# 3_6_1--esp32_-_0825.net
KiCad netlist of a schematic drawn in EasyEDA Pro
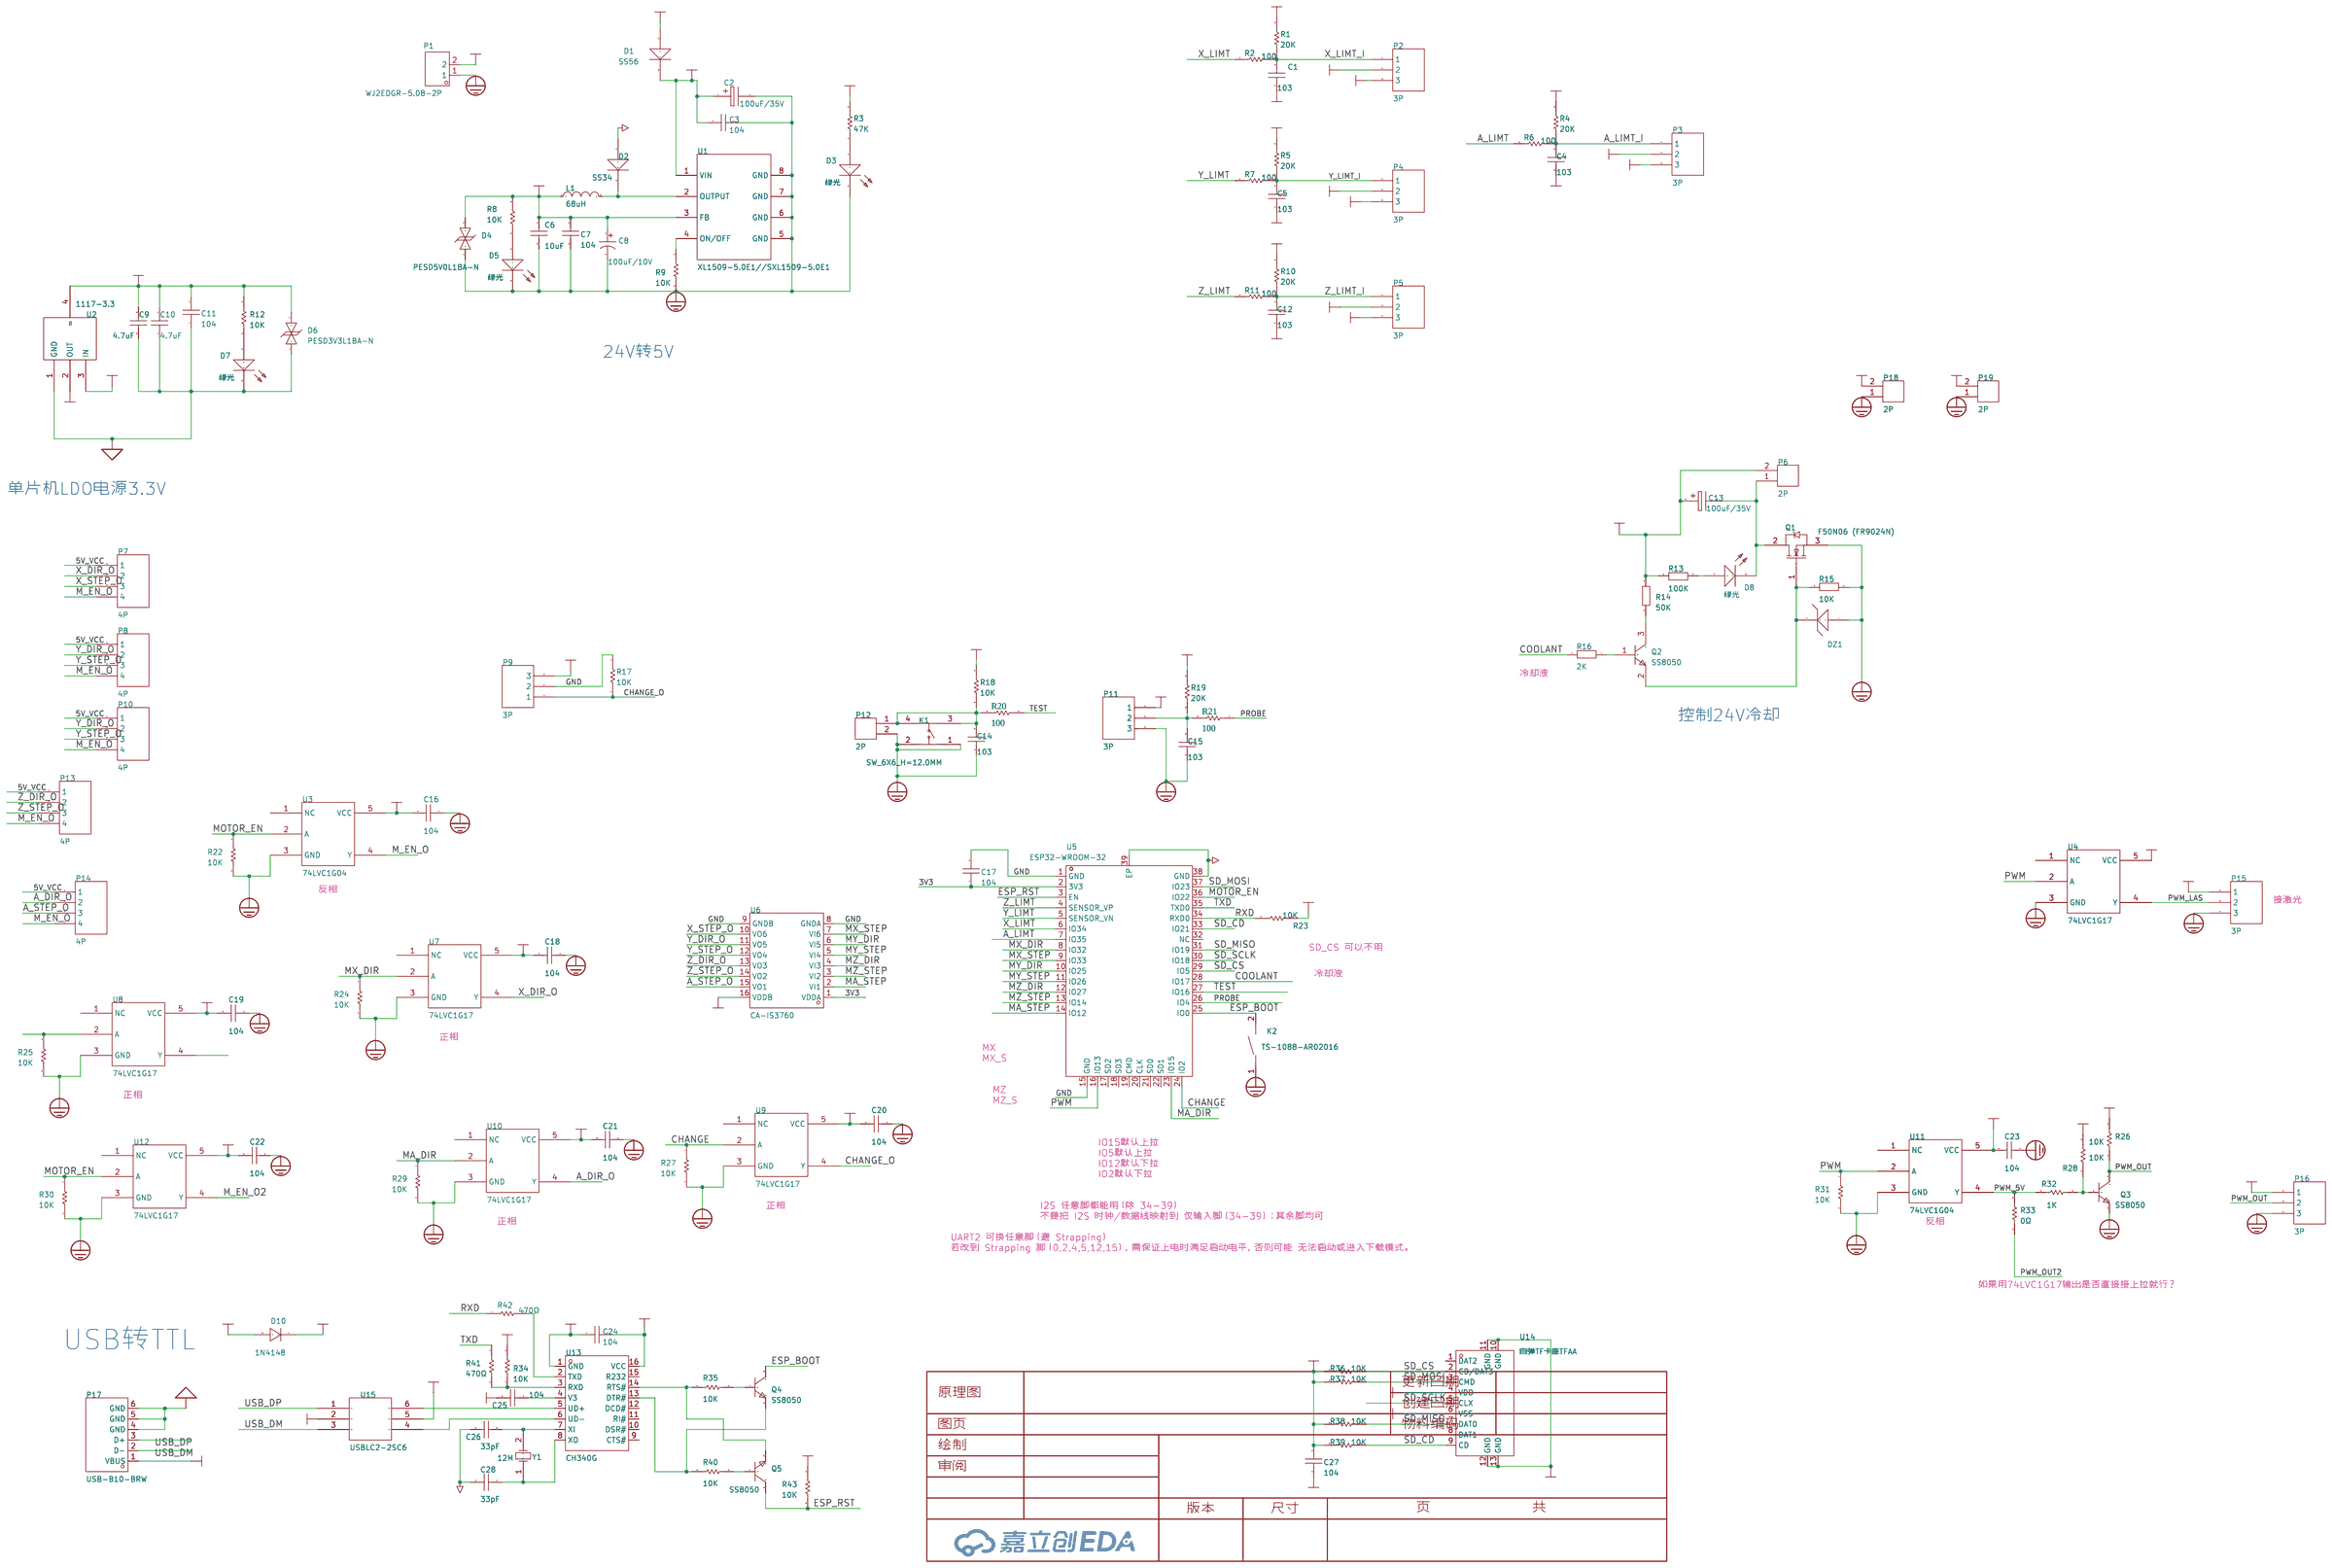
[diagram p0: schematic sheet]

(export (version "E")
  (design (tool "Eeschema 10.0.6"))
  (components
    (comp (ref "C1") (value "103") (footprint "easyedapro:11") (libsource (lib "easyedapro") (part "CAP")))
    (comp (ref "C2")
      (value "100uF/35V")
      (footprint "easyedapro:电解电容贴片10x10")
      (libsource (lib "easyedapro") (part "ELECTRO1"))
    )
    (comp (ref "C3")
      (value "104")
      (footprint "easyedapro:0603C")
      (description "Capacitor (Semiconductor SIM Model)")
      (libsource (lib "easyedapro") (part "Cap Semi"))
    )
    (comp (ref "C4") (value "103") (footprint "easyedapro:11") (libsource (lib "easyedapro") (part "CAP")))
    (comp (ref "C5") (value "103") (footprint "easyedapro:11") (libsource (lib "easyedapro") (part "CAP")))
    (comp (ref "C6") (value "10uF") (libsource (lib "") (part "CAP_1")))
    (comp (ref "C7")
      (value "104")
      (footprint "easyedapro:0603C")
      (description "Capacitor (Semiconductor SIM Model)")
      (libsource (lib "easyedapro") (part "Cap Semi"))
    )
    (comp (ref "C8")
      (value "100uF/10V")
      (footprint "easyedapro:CAP-SMD_BD5.0-L5.3-W5.3-RD")
      (fields (field (name "Manufacturer Part") "CS1A101M-CRD54") (field (name "Manufacturer") "ST(先科)"))
      (libsource (lib "easyedapro") (part "CS1A101M-CRD54"))
    )
    (comp (ref "C9") (value "4.7uF") (libsource (lib "") (part "CAP_1")))
    (comp (ref "C10") (value "4.7uF") (libsource (lib "") (part "CAP_1")))
    (comp (ref "C11")
      (value "104")
      (footprint "easyedapro:0603C")
      (description "Capacitor (Semiconductor SIM Model)")
      (libsource (lib "easyedapro") (part "Cap Semi"))
    )
    (comp (ref "C12") (value "103") (footprint "easyedapro:11") (libsource (lib "easyedapro") (part "CAP")))
    (comp (ref "C13")
      (value "100uF/35V")
      (footprint "easyedapro:电解电容贴片10x10")
      (libsource (lib "easyedapro") (part "ELECTRO1"))
    )
    (comp (ref "C14") (value "103") (footprint "easyedapro:11") (libsource (lib "easyedapro") (part "CAP")))
    (comp (ref "C15") (value "103") (footprint "easyedapro:11") (libsource (lib "easyedapro") (part "CAP")))
    (comp (ref "C16")
      (value "104")
      (footprint "easyedapro:0603C")
      (description "Capacitor (Semiconductor SIM Model)")
      (libsource (lib "easyedapro") (part "Cap Semi"))
    )
    (comp (ref "C17")
      (value "104")
      (footprint "easyedapro:0603C")
      (description "Capacitor (Semiconductor SIM Model)")
      (libsource (lib "easyedapro") (part "Cap Semi"))
    )
    (comp (ref "C18")
      (value "104")
      (footprint "easyedapro:0603C")
      (description "Capacitor (Semiconductor SIM Model)")
      (libsource (lib "easyedapro") (part "Cap Semi"))
    )
    (comp (ref "C19")
      (value "104")
      (footprint "easyedapro:0603C")
      (description "Capacitor (Semiconductor SIM Model)")
      (libsource (lib "easyedapro") (part "Cap Semi"))
    )
    (comp (ref "C20")
      (value "104")
      (footprint "easyedapro:0603C")
      (description "Capacitor (Semiconductor SIM Model)")
      (libsource (lib "easyedapro") (part "Cap Semi"))
    )
    (comp (ref "C21")
      (value "104")
      (footprint "easyedapro:0603C")
      (description "Capacitor (Semiconductor SIM Model)")
      (libsource (lib "easyedapro") (part "Cap Semi"))
    )
    (comp (ref "C22")
      (value "104")
      (footprint "easyedapro:0603C")
      (description "Capacitor (Semiconductor SIM Model)")
      (libsource (lib "easyedapro") (part "Cap Semi"))
    )
    (comp (ref "C23")
      (value "104")
      (footprint "easyedapro:0603C")
      (description "Capacitor (Semiconductor SIM Model)")
      (libsource (lib "easyedapro") (part "Cap Semi"))
    )
    (comp (ref "C24")
      (value "104")
      (footprint "easyedapro:0603C")
      (description "Capacitor (Semiconductor SIM Model)")
      (libsource (lib "easyedapro") (part "Cap Semi"))
    )
    (comp (ref "C25")
      (value "104")
      (footprint "easyedapro:0603C")
      (description "Capacitor (Semiconductor SIM Model)")
      (libsource (lib "easyedapro") (part "Cap Semi"))
    )
    (comp (ref "C26")
      (value "18pF")
      (footprint "easyedapro:0603C")
      (description "Capacitor (Semiconductor SIM Model)")
      (libsource (lib "easyedapro") (part "Cap Semi"))
    )
    (comp (ref "C27")
      (value "104")
      (footprint "easyedapro:11")
      (description "Capacitor (Semiconductor SIM Model)")
      (libsource (lib "easyedapro") (part "Cap Semi"))
    )
    (comp (ref "C28")
      (value "18pF")
      (footprint "easyedapro:0603C")
      (description "Capacitor (Semiconductor SIM Model)")
      (libsource (lib "easyedapro") (part "Cap Semi"))
    )
    (comp (ref "D1") (value "SS56") (footprint "easyedapro:SMA") (libsource (lib "") (part "1N4148_1")))
    (comp (ref "D2") (value "SS34") (libsource (lib "easyedapro") (part "1N4148")))
    (comp (ref "D3")
      (value "绿光")
      (footprint "easyedapro:0603LED")
      (libsource (lib "easyedapro") (part "LED"))
    )
    (comp (ref "D4")
      (value "PESD5V0L1BA-N")
      (footprint "easyedapro:SOD-523_L1.2-W0.8-LS1.6-BI")
      (description "极性:Bidirectional;反向关断电压（典型值）:5V (Max);击穿电压（最小值）:6V;箝位电压:15V;峰值脉冲电流（10/1000us）:5A (8/20us);")
      (fields (field (name "Manufacturer") "BORN伯恩半导体"))
      (libsource (lib "easyedapro") (part "PESD5V0S1BBN"))
    )
    (comp (ref "D5")
      (value "绿光")
      (footprint "easyedapro:0603LED")
      (libsource (lib "easyedapro") (part "LED"))
    )
    (comp (ref "D6")
      (value "PESD3V3L1BA-N")
      (footprint "easyedapro:SOD-523_L1.2-W0.8-LS1.6-BI")
      (description "极性:Bidirectional;反向关断电压（典型值）:5V (Max);击穿电压（最小值）:6V;箝位电压:15V;峰值脉冲电流（10/1000us）:5A (8/20us);")
      (fields (field (name "Manufacturer") "BORN伯恩半导体"))
      (libsource (lib "easyedapro") (part "PESD5V0S1BBN"))
    )
    (comp (ref "D7")
      (value "绿光")
      (footprint "easyedapro:0603LED")
      (libsource (lib "easyedapro") (part "LED"))
    )
    (comp (ref "D8")
      (value "绿光")
      (footprint "easyedapro:0603LED")
      (libsource (lib "easyedapro") (part "LED"))
    )
    (comp (ref "D10")
      (value "1N4148")
      (footprint "easyedapro:SOD-123_L2.8-W1.8-LS3.7-RD")
      (fields (field (name "Manufacturer") "MCC(美微科)"))
      (libsource (lib "easyedapro") (part "1N4148W-TP"))
    )
    (comp (ref "DZ1") (value "--ѹ------SMAZ10V") (libsource (lib "easyedapro") (part "ѹ")))
    (comp (ref "K1")
      (value "SW_6X6_H=12.0MM")
      (footprint "easyedapro:KEY-SMD_4P-L6.0-W6.0-P4.50-LS9.0")
      (libsource (lib "easyedapro") (part "SW_6X6_H=12.0MM"))
    )
    (comp (ref "K2")
      (value "TS-1088-AR02016")
      (footprint "easyedapro:SW-SMD_L3.9-W3.0-P4.45")
      (fields (field (name "Manufacturer") "XUNPU(讯普)"))
      (libsource (lib "easyedapro") (part "TS-1088-AR02016"))
    )
    (comp (ref "L1")
      (value "68uH")
      (footprint "easyedapro:IND-SMD_L7.0-W7.0_SMDRI74-330MT")
      (description "电感值:33uH;精度:±20%;额定电流:960mA;饱和电流(Isat):1.8A;类型:屏蔽电感;")
      (fields (field (name "Manufacturer Part") "SMDRI74-330MT") (field (name "Manufacturer") "SXN(顺翔诺)"))
      (libsource (lib "easyedapro") (part "SMDRI74-330MT"))
    )
    (comp (ref "P1")
      (value "WJ2EDGR-5.08-2P")
      (footprint "easyedapro:CONN-TH_WJ2EDGR-5.08-2P")
      (description "每排PIN数:2;安装方式:弯针;排数:1;间距:5.08mm;连接器类型:板端/插座-开口;")
      (fields (field (name "Manufacturer") "KANGNEX(康奈克斯电气)"))
      (libsource (lib "easyedapro") (part "WJ2EDGR-5.08-2P"))
    )
    (comp (ref "P2")
      (value "3P")
      (footprint "easyedapro:HDR1X3_CON")
      (libsource (lib "easyedapro") (part "3P"))
    )
    (comp (ref "P3")
      (value "3P")
      (footprint "easyedapro:HDR1X3_CON")
      (libsource (lib "easyedapro") (part "3P"))
    )
    (comp (ref "P4")
      (value "3P")
      (footprint "easyedapro:HDR1X3_CON")
      (libsource (lib "easyedapro") (part "3P"))
    )
    (comp (ref "P5")
      (value "3P")
      (footprint "easyedapro:HDR1X3_CON")
      (libsource (lib "easyedapro") (part "3P"))
    )
    (comp (ref "P6")
      (value "2P")
      (footprint "easyedapro:HDR1X2_CON")
      (libsource (lib "easyedapro") (part "2P"))
    )
    (comp (ref "P7")
      (value "4P")
      (footprint "easyedapro:HDR1X4_CON")
      (libsource (lib "easyedapro") (part "4P"))
    )
    (comp (ref "P8")
      (value "4P")
      (footprint "easyedapro:HDR1X4_CON")
      (libsource (lib "easyedapro") (part "4P"))
    )
    (comp (ref "P9")
      (value "3P")
      (footprint "easyedapro:HDR1X3_CON")
      (libsource (lib "easyedapro") (part "3P"))
    )
    (comp (ref "P10")
      (value "4P")
      (footprint "easyedapro:HDR1X4_CON")
      (libsource (lib "easyedapro") (part "4P"))
    )
    (comp (ref "P11")
      (value "3P")
      (footprint "easyedapro:HDR1X3_CON")
      (libsource (lib "easyedapro") (part "3P"))
    )
    (comp (ref "P12")
      (value "2P")
      (footprint "easyedapro:HDR1X2_CON")
      (libsource (lib "easyedapro") (part "2P"))
    )
    (comp (ref "P13")
      (value "4P")
      (footprint "easyedapro:HDR1X4_CON")
      (libsource (lib "easyedapro") (part "4P"))
    )
    (comp (ref "P14")
      (value "4P")
      (footprint "easyedapro:HDR1X4_CON")
      (libsource (lib "easyedapro") (part "4P"))
    )
    (comp (ref "P15")
      (value "3P")
      (footprint "easyedapro:HDR1X3_CON")
      (libsource (lib "easyedapro") (part "3P"))
    )
    (comp (ref "P16")
      (value "3P")
      (footprint "easyedapro:HDR1X3_CON")
      (libsource (lib "easyedapro") (part "3P"))
    )
    (comp (ref "P17")
      (value "USB-B10-BRW")
      (footprint "easyedapro:USB-B-TH_USB-B10-BRW")
      (fields (field (name "Manufacturer") "XUNPU(讯普)"))
      (libsource (lib "easyedapro") (part "USB-B10-BRW"))
    )
    (comp (ref "P18")
      (value "2P")
      (footprint "easyedapro:HDR1X2_CON")
      (libsource (lib "easyedapro") (part "2P"))
    )
    (comp (ref "P19")
      (value "2P")
      (footprint "easyedapro:HDR1X2_CON")
      (libsource (lib "easyedapro") (part "2P"))
    )
    (comp (ref "Q1")
      (value "F50N06 (FR9024N)")
      (footprint "easyedapro:TO-252")
      (description "N-Channel Power MOSFET")
      (libsource (lib "easyedapro") (part "NMOS-2"))
    )
    (comp (ref "Q2")
      (value "SS8050")
      (footprint "easyedapro:SOT-23")
      (description "NPN General Purpose Amplifier")
      (libsource (lib "easyedapro") (part "2N3904"))
    )
    (comp (ref "Q3")
      (value "SS8050")
      (footprint "easyedapro:SOT-23-3_L2.9-W1.3-P1.90-LS2.4-BR")
      (fields (field (name "Manufacturer") "CJ（江苏长电/长晶）"))
      (libsource (lib "easyedapro") (part "SS8050_C2150"))
    )
    (comp (ref "Q4")
      (value "SS8050")
      (footprint "easyedapro:SOT-23-3_L2.9-W1.3-P1.90-LS2.4-BR")
      (fields (field (name "Manufacturer") "Doeshare(德芯)"))
      (libsource (lib "easyedapro") (part "SS8050_C2931717"))
    )
    (comp (ref "Q5")
      (value "SS8050")
      (footprint "easyedapro:SOT-23-3_L2.9-W1.3-P1.90-LS2.4-BR")
      (fields (field (name "Manufacturer") "Doeshare(德芯)"))
      (libsource (lib "easyedapro") (part "SS8050_C2931717"))
    )
    (comp (ref "R1")
      (value "20K")
      (footprint "easyedapro:10")
      (description "Resistor")
      (libsource (lib "") (part "RES_1"))
    )
    (comp (ref "R2")
      (value "100")
      (footprint "easyedapro:10")
      (description "Resistor")
      (libsource (lib "") (part "RES_1"))
    )
    (comp (ref "R3")
      (value "47K")
      (footprint "easyedapro:0603R")
      (description "Resistor")
      (libsource (lib "") (part "RES_1"))
    )
    (comp (ref "R4")
      (value "20K")
      (footprint "easyedapro:10")
      (description "Resistor")
      (libsource (lib "") (part "RES_1"))
    )
    (comp (ref "R5")
      (value "20K")
      (footprint "easyedapro:10")
      (description "Resistor")
      (libsource (lib "") (part "RES_1"))
    )
    (comp (ref "R6")
      (value "100")
      (footprint "easyedapro:10")
      (description "Resistor")
      (libsource (lib "") (part "RES_1"))
    )
    (comp (ref "R7")
      (value "100")
      (footprint "easyedapro:10")
      (description "Resistor")
      (libsource (lib "") (part "RES_1"))
    )
    (comp (ref "R8")
      (value "10K")
      (footprint "easyedapro:0603R")
      (description "Resistor")
      (libsource (lib "") (part "RES_1"))
    )
    (comp (ref "R9")
      (value "10K")
      (footprint "easyedapro:0603R")
      (description "Resistor")
      (libsource (lib "") (part "RES_1"))
    )
    (comp (ref "R10")
      (value "20K")
      (footprint "easyedapro:10")
      (description "Resistor")
      (libsource (lib "") (part "RES_1"))
    )
    (comp (ref "R11")
      (value "100")
      (footprint "easyedapro:10")
      (description "Resistor")
      (libsource (lib "") (part "RES_1"))
    )
    (comp (ref "R12")
      (value "10K")
      (footprint "easyedapro:0603R")
      (description "Resistor")
      (libsource (lib "") (part "RES_1"))
    )
    (comp (ref "R13")
      (value "100K")
      (footprint "easyedapro:0603R")
      (libsource (lib "easyedapro") (part "res"))
    )
    (comp (ref "R14")
      (value "50K")
      (footprint "easyedapro:0603R")
      (libsource (lib "easyedapro") (part "res"))
    )
    (comp (ref "R15")
      (value "10K")
      (footprint "easyedapro:0603R")
      (libsource (lib "easyedapro") (part "res"))
    )
    (comp (ref "R16") (value "2K") (footprint "easyedapro:0603R") (libsource (lib "easyedapro") (part "res")))
    (comp (ref "R17")
      (value "10K")
      (footprint "easyedapro:0603R")
      (description "Resistor")
      (libsource (lib "") (part "RES_1"))
    )
    (comp (ref "R18")
      (value "10K")
      (footprint "easyedapro:0603R")
      (description "Resistor")
      (libsource (lib "") (part "RES_1"))
    )
    (comp (ref "R19")
      (value "10K")
      (footprint "easyedapro:0603R")
      (description "Resistor")
      (libsource (lib "") (part "RES_1"))
    )
    (comp (ref "R20")
      (value "100")
      (description "Resistor")
      (fields (field (name "Publisher") "Altium Limited"))
      (libsource (lib "easyedapro") (part "RES"))
    )
    (comp (ref "R21")
      (value "100")
      (description "Resistor")
      (fields (field (name "Publisher") "Altium Limited"))
      (libsource (lib "easyedapro") (part "RES"))
    )
    (comp (ref "R22")
      (value "10K")
      (description "Resistor")
      (fields (field (name "Publisher") "Altium Limited"))
      (libsource (lib "easyedapro") (part "RES"))
    )
    (comp (ref "R23")
      (value "10K")
      (footprint "easyedapro:0603R")
      (description "Resistor")
      (libsource (lib "") (part "RES_1"))
    )
    (comp (ref "R24")
      (value "10K")
      (description "Resistor")
      (fields (field (name "Publisher") "Altium Limited"))
      (libsource (lib "easyedapro") (part "RES"))
    )
    (comp (ref "R25")
      (value "10K")
      (description "Resistor")
      (fields (field (name "Publisher") "Altium Limited"))
      (libsource (lib "easyedapro") (part "RES"))
    )
    (comp (ref "R26")
      (value "10K")
      (description "Resistor")
      (fields (field (name "Publisher") "Altium Limited"))
      (libsource (lib "easyedapro") (part "RES"))
    )
    (comp (ref "R27")
      (value "10K")
      (description "Resistor")
      (fields (field (name "Publisher") "Altium Limited"))
      (libsource (lib "easyedapro") (part "RES"))
    )
    (comp (ref "R28")
      (value "10K")
      (description "Resistor")
      (fields (field (name "Publisher") "Altium Limited"))
      (libsource (lib "easyedapro") (part "RES"))
    )
    (comp (ref "R29")
      (value "10K")
      (description "Resistor")
      (fields (field (name "Publisher") "Altium Limited"))
      (libsource (lib "easyedapro") (part "RES"))
    )
    (comp (ref "R30")
      (value "10K")
      (description "Resistor")
      (fields (field (name "Publisher") "Altium Limited"))
      (libsource (lib "easyedapro") (part "RES"))
    )
    (comp (ref "R31")
      (value "10K")
      (description "Resistor")
      (fields (field (name "Publisher") "Altium Limited"))
      (libsource (lib "easyedapro") (part "RES"))
    )
    (comp (ref "R32")
      (value "1K")
      (description "Resistor")
      (fields (field (name "Publisher") "Altium Limited"))
      (libsource (lib "easyedapro") (part "RES"))
    )
    (comp (ref "R33")
      (value "0Ω")
      (description "Resistor")
      (fields (field (name "Publisher") "Altium Limited"))
      (libsource (lib "easyedapro") (part "RES"))
    )
    (comp (ref "R34")
      (value "10K")
      (footprint "easyedapro:0603R")
      (description "Resistor")
      (libsource (lib "") (part "RES_1"))
    )
    (comp (ref "R35")
      (value "10K")
      (footprint "easyedapro:0603R")
      (description "Resistor")
      (libsource (lib "") (part "RES_1"))
    )
    (comp (ref "R36")
      (value "10K")
      (footprint "easyedapro:10")
      (description "Resistor")
      (libsource (lib "") (part "RES_1"))
    )
    (comp (ref "R37")
      (value "10K")
      (footprint "easyedapro:10")
      (description "Resistor")
      (libsource (lib "") (part "RES_1"))
    )
    (comp (ref "R38")
      (value "10K")
      (footprint "easyedapro:10")
      (description "Resistor")
      (libsource (lib "") (part "RES_1"))
    )
    (comp (ref "R39")
      (value "10K")
      (footprint "easyedapro:10")
      (description "Resistor")
      (libsource (lib "") (part "RES_1"))
    )
    (comp (ref "R40")
      (value "10K")
      (footprint "easyedapro:0603R")
      (description "Resistor")
      (libsource (lib "") (part "RES_1"))
    )
    (comp (ref "R41")
      (value "470Ω")
      (description "Resistor")
      (fields (field (name "Publisher") "Altium Limited"))
      (libsource (lib "easyedapro") (part "RES"))
    )
    (comp (ref "R42")
      (value "470Ω")
      (description "Resistor")
      (fields (field (name "Publisher") "Altium Limited"))
      (libsource (lib "easyedapro") (part "RES"))
    )
    (comp (ref "R43")
      (value "10K")
      (description "Resistor")
      (fields (field (name "Publisher") "Altium Limited"))
      (libsource (lib "easyedapro") (part "RES"))
    )
    (comp (ref "U1")
      (value "XL1509-5.0E1//SXL1509-5.0E1")
      (footprint "easyedapro:SOIC-8_L5.0-W4.0-P1.27-LS6.0-BL")
      (description "功能类型:降压型;同步整流:-;输出通道数:-;拓扑结构:-;输入电压:-;输出电流(最大值):-;开关频率:-;")
      (fields (field (name "Manufacturer") "XLSEMI(芯龙)"))
      (libsource (lib "easyedapro") (part "XL1509-5.0E1"))
    )
    (comp (ref "U2")
      (value "1117-3.3")
      (footprint "easyedapro:SOT-223")
      (libsource (lib "easyedapro") (part "LM1117"))
    )
    (comp (ref "U3")
      (value "74LVC1G04")
      (footprint "easyedapro:SMD8")
      (libsource (lib "easyedapro") (part "74LVC1G04"))
    )
    (comp (ref "U4")
      (value "74LVC1G17")
      (footprint "easyedapro:SMD8")
      (libsource (lib "easyedapro") (part "74LVC1G04"))
    )
    (comp (ref "U5")
      (value "ESP32-WROOM-32")
      (footprint "easyedapro:WIFIM-SMD_ESP-WROOM-32")
      (description "WiFi+双模蓝牙 双核CPU 网口 顶配MCU 低功耗蓝牙 ESP32系列ESP-WROOM-32模组/ESP-32S 4MB")
      (fields (field (name "Manufacturer") "ESPRESSIF(乐鑫)"))
      (libsource (lib "easyedapro") (part "ESP-WROOM-32"))
    )
    (comp (ref "U6")
      (value "CA-IS3760")
      (footprint "easyedapro:SOIC-16_L9.9-W3.9-P1.27-LS6.0-BL")
      (fields (field (name "Manufacturer") "Chipanalog(川土微)"))
      (libsource (lib "easyedapro") (part "CA-IS3760HN"))
    )
    (comp (ref "U7")
      (value "74LVC1G17")
      (footprint "easyedapro:SMD8")
      (libsource (lib "easyedapro") (part "74LVC1G04"))
    )
    (comp (ref "U8")
      (value "74LVC1G17")
      (footprint "easyedapro:SMD8")
      (libsource (lib "easyedapro") (part "74LVC1G04"))
    )
    (comp (ref "U9")
      (value "74LVC1G17")
      (footprint "easyedapro:SMD8")
      (libsource (lib "easyedapro") (part "74LVC1G04"))
    )
    (comp (ref "U10")
      (value "74LVC1G17")
      (footprint "easyedapro:SMD8")
      (libsource (lib "easyedapro") (part "74LVC1G04"))
    )
    (comp (ref "U11")
      (value "74LVC1G04")
      (footprint "easyedapro:SMD8")
      (libsource (lib "easyedapro") (part "74LVC1G04"))
    )
    (comp (ref "U12")
      (value "74LVC1G17")
      (footprint "easyedapro:SMD8")
      (libsource (lib "easyedapro") (part "74LVC1G04"))
    )
    (comp (ref "U13")
      (value "CH340G")
      (footprint "easyedapro:SOIC-16_L9.9-W3.9-P1.27-LS6.0-BL")
      (description "应用功能:收发器;接口协议:USB 2.0;数据速率:2Mbps;")
      (fields (field (name "Manufacturer") "WCH(南京沁恒)"))
      (libsource (lib "easyedapro") (part "CH340G"))
    )
    (comp (ref "U14")
      (value "自弹TF卡座TFAA")
      (footprint "easyedapro:SIM-SMD_C9900015645")
      (libsource (lib "easyedapro") (part "自弹TF卡座TFAA"))
    )
    (comp (ref "U15")
      (value "USBLC2-2SC6")
      (footprint "easyedapro:SOT-23-6")
      (libsource (lib "easyedapro") (part "DIP6"))
    )
    (comp (ref "Y1")
      (value "12M")
      (footprint "easyedapro:晶振贴片49SSMD")
      (description "Crystal Oscillator")
      (libsource (lib "easyedapro") (part "XTAL"))
    )
  )
  (nets
    (net (code "1") (name "/A_DIR_O") (class "Default")
      (node (ref "P14") (pin "2") (pinfunction "2_2") (pintype "unspecified"))
      (node (ref "U10") (pin "4") (pinfunction "Y_4") (pintype "unspecified"))
    )
    (net (code "2") (name "/A_LIMT") (class "Default")
      (node (ref "R6") (pin "2") (pinfunction "2_2") (pintype "unspecified"))
      (node (ref "U5") (pin "7") (pinfunction "IO35_7") (pintype "unspecified"))
    )
    (net (code "3") (name "/A_LIMT_I") (class "Default")
      (node (ref "C4") (pin "2") (pinfunction "2_2") (pintype "unspecified"))
      (node (ref "P3") (pin "1") (pinfunction "1_1") (pintype "unspecified"))
      (node (ref "R4") (pin "1") (pinfunction "1_1") (pintype "unspecified"))
      (node (ref "R6") (pin "1") (pinfunction "1_1") (pintype "unspecified"))
    )
    (net (code "4") (name "/A_STEP_O") (class "Default")
      (node (ref "P14") (pin "3") (pinfunction "3_3") (pintype "unspecified"))
      (node (ref "U6") (pin "15") (pinfunction "VO1_15") (pintype "unspecified"))
    )
    (net (code "5") (name "/CHANGE") (class "Default")
      (node (ref "R27") (pin "1") (pinfunction "1_1") (pintype "input"))
      (node (ref "U5") (pin "24") (pinfunction "IO2_24") (pintype "unspecified"))
      (node (ref "U9") (pin "2") (pinfunction "A_2") (pintype "unspecified"))
    )
    (net (code "6") (name "/CHANGE_O") (class "Default")
      (node (ref "P9") (pin "1") (pinfunction "1_1") (pintype "unspecified"))
      (node (ref "R17") (pin "2") (pinfunction "2_2") (pintype "unspecified"))
      (node (ref "U9") (pin "4") (pinfunction "Y_4") (pintype "unspecified"))
    )
    (net (code "7") (name "/COOLANT") (class "Default")
      (node (ref "R16") (pin "2") (pintype "unspecified"))
      (node (ref "U5") (pin "28") (pinfunction "IO17_28") (pintype "unspecified"))
    )
    (net (code "8") (name "/ESP_BOOT") (class "Default")
      (node (ref "K2") (pin "2") (pinfunction "2_2") (pintype "unspecified"))
      (node (ref "Q4") (pin "3") (pinfunction "C_3") (pintype "unspecified"))
      (node (ref "U5") (pin "25") (pinfunction "IO0_25") (pintype "unspecified"))
    )
    (net (code "9") (name "/ESP_RST") (class "Default")
      (node (ref "Q5") (pin "3") (pinfunction "C_3") (pintype "unspecified"))
      (node (ref "R43") (pin "2") (pinfunction "2_2") (pintype "input"))
      (node (ref "U5") (pin "3") (pinfunction "EN_3") (pintype "unspecified"))
    )
    (net (code "10") (name "/MA_DIR") (class "Default")
      (node (ref "R29") (pin "1") (pinfunction "1_1") (pintype "input"))
      (node (ref "U10") (pin "2") (pinfunction "A_2") (pintype "unspecified"))
      (node (ref "U5") (pin "23") (pinfunction "IO15_23") (pintype "unspecified"))
    )
    (net (code "11") (name "/MA_STEP") (class "Default")
      (node (ref "U5") (pin "14") (pinfunction "IO12_14") (pintype "unspecified"))
      (node (ref "U6") (pin "2") (pinfunction "VI1_2") (pintype "unspecified"))
    )
    (net (code "12") (name "/MOTOR_EN") (class "Default")
      (node (ref "R22") (pin "1") (pinfunction "1_1") (pintype "input"))
      (node (ref "R30") (pin "1") (pinfunction "1_1") (pintype "input"))
      (node (ref "U12") (pin "2") (pinfunction "A_2") (pintype "unspecified"))
      (node (ref "U3") (pin "2") (pinfunction "A_2") (pintype "unspecified"))
      (node (ref "U5") (pin "36") (pinfunction "IO22_36") (pintype "unspecified"))
    )
    (net (code "13") (name "/MX_DIR") (class "Default")
      (node (ref "R24") (pin "1") (pinfunction "1_1") (pintype "input"))
      (node (ref "U5") (pin "8") (pinfunction "IO32_8") (pintype "unspecified"))
      (node (ref "U7") (pin "2") (pinfunction "A_2") (pintype "unspecified"))
    )
    (net (code "14") (name "/MX_STEP") (class "Default")
      (node (ref "U5") (pin "9") (pinfunction "IO33_9") (pintype "unspecified"))
      (node (ref "U6") (pin "7") (pinfunction "VI6_7") (pintype "unspecified"))
    )
    (net (code "15") (name "/MY_DIR") (class "Default")
      (node (ref "U5") (pin "10") (pinfunction "IO25_10") (pintype "unspecified"))
      (node (ref "U6") (pin "6") (pinfunction "VI5_6") (pintype "unspecified"))
    )
    (net (code "16") (name "/MY_STEP") (class "Default")
      (node (ref "U5") (pin "11") (pinfunction "IO26_11") (pintype "unspecified"))
      (node (ref "U6") (pin "5") (pinfunction "VI4_5") (pintype "unspecified"))
    )
    (net (code "17") (name "/MZ_DIR") (class "Default")
      (node (ref "U5") (pin "12") (pinfunction "IO27_12") (pintype "unspecified"))
      (node (ref "U6") (pin "4") (pinfunction "VI3_4") (pintype "unspecified"))
    )
    (net (code "18") (name "/MZ_STEP") (class "Default")
      (node (ref "U5") (pin "13") (pinfunction "IO14_13") (pintype "unspecified"))
      (node (ref "U6") (pin "3") (pinfunction "VI2_3") (pintype "unspecified"))
    )
    (net (code "19") (name "/M_EN_O") (class "Default")
      (node (ref "P10") (pin "4") (pinfunction "4_4") (pintype "unspecified"))
      (node (ref "P13") (pin "4") (pinfunction "4_4") (pintype "unspecified"))
      (node (ref "P14") (pin "4") (pinfunction "4_4") (pintype "unspecified"))
      (node (ref "P7") (pin "4") (pinfunction "4_4") (pintype "unspecified"))
      (node (ref "P8") (pin "4") (pinfunction "4_4") (pintype "unspecified"))
      (node (ref "U3") (pin "4") (pinfunction "Y_4") (pintype "unspecified"))
    )
    (net (code "20") (name "/M_EN_O2") (class "Default")
      (node (ref "U12") (pin "4") (pinfunction "Y_4") (pintype "unspecified"))
    )
    (net (code "21") (name "/PROBE") (class "Default")
      (node (ref "R21") (pin "1") (pinfunction "1_1") (pintype "input"))
      (node (ref "U5") (pin "26") (pinfunction "IO4_26") (pintype "unspecified"))
    )
    (net (code "22") (name "/PWM") (class "Default")
      (node (ref "R31") (pin "1") (pinfunction "1_1") (pintype "input"))
      (node (ref "U11") (pin "2") (pinfunction "A_2") (pintype "unspecified"))
      (node (ref "U4") (pin "2") (pinfunction "A_2") (pintype "unspecified"))
      (node (ref "U5") (pin "16") (pinfunction "IO13_16") (pintype "unspecified"))
    )
    (net (code "23") (name "/PWM_5V") (class "Default")
      (node (ref "R32") (pin "1") (pinfunction "1_1") (pintype "input"))
      (node (ref "R33") (pin "2") (pinfunction "2_2") (pintype "input"))
      (node (ref "U11") (pin "4") (pinfunction "Y_4") (pintype "unspecified"))
    )
    (net (code "24") (name "/PWM_LAS") (class "Default")
      (node (ref "P15") (pin "2") (pinfunction "2_2") (pintype "unspecified"))
      (node (ref "U4") (pin "4") (pinfunction "Y_4") (pintype "unspecified"))
    )
    (net (code "25") (name "/PWM_OUT") (class "Default")
      (node (ref "P16") (pin "2") (pinfunction "2_2") (pintype "unspecified"))
      (node (ref "Q3") (pin "3") (pinfunction "C_3") (pintype "input"))
      (node (ref "R26") (pin "1") (pinfunction "1_1") (pintype "input"))
    )
    (net (code "26") (name "/PWM_OUT2") (class "Default")
      (node (ref "R33") (pin "1") (pinfunction "1_1") (pintype "input"))
    )
    (net (code "27") (name "/RXD") (class "Default")
      (node (ref "R23") (pin "2") (pinfunction "2_2") (pintype "unspecified"))
      (node (ref "R42") (pin "1") (pinfunction "1_1") (pintype "input"))
      (node (ref "U5") (pin "34") (pinfunction "RXD0_34") (pintype "unspecified"))
    )
    (net (code "28") (name "/SD_CD") (class "Default")
      (node (ref "R39") (pin "1") (pinfunction "1_1") (pintype "unspecified"))
      (node (ref "U14") (pin "9") (pinfunction "CD_9") (pintype "unspecified"))
      (node (ref "U5") (pin "33") (pinfunction "IO21_33") (pintype "unspecified"))
    )
    (net (code "29") (name "/SD_CS") (class "Default")
      (node (ref "R36") (pin "1") (pinfunction "1_1") (pintype "unspecified"))
      (node (ref "U14") (pin "2") (pinfunction "CD/DAT3_2") (pintype "unspecified"))
      (node (ref "U5") (pin "29") (pinfunction "IO5_29") (pintype "unspecified"))
    )
    (net (code "30") (name "/SD_MISO") (class "Default")
      (node (ref "R38") (pin "1") (pinfunction "1_1") (pintype "unspecified"))
      (node (ref "U14") (pin "7") (pinfunction "DAT0_7") (pintype "unspecified"))
      (node (ref "U5") (pin "31") (pinfunction "IO19_31") (pintype "unspecified"))
    )
    (net (code "31") (name "/SD_MOSI") (class "Default")
      (node (ref "R37") (pin "1") (pinfunction "1_1") (pintype "unspecified"))
      (node (ref "U14") (pin "3") (pinfunction "CMD_3") (pintype "unspecified"))
      (node (ref "U5") (pin "37") (pinfunction "IO23_37") (pintype "unspecified"))
    )
    (net (code "32") (name "/SD_SCLK") (class "Default")
      (node (ref "U14") (pin "5") (pinfunction "CLX_5") (pintype "unspecified"))
      (node (ref "U5") (pin "30") (pinfunction "IO18_30") (pintype "unspecified"))
    )
    (net (code "33") (name "/TEST") (class "Default")
      (node (ref "R20") (pin "1") (pinfunction "1_1") (pintype "input"))
      (node (ref "U5") (pin "27") (pinfunction "IO16_27") (pintype "unspecified"))
    )
    (net (code "34") (name "/TXD") (class "Default")
      (node (ref "R41") (pin "1") (pinfunction "1_1") (pintype "input"))
      (node (ref "U5") (pin "35") (pinfunction "TXD0_35") (pintype "unspecified"))
    )
    (net (code "35") (name "/USB_DM") (class "Default")
      (node (ref "P17") (pin "2") (pinfunction "D-_2") (pintype "unspecified"))
      (node (ref "U15") (pin "3") (pinfunction "3_3") (pintype "unspecified"))
    )
    (net (code "36") (name "/USB_DP") (class "Default")
      (node (ref "P17") (pin "3") (pinfunction "D+_3") (pintype "unspecified"))
      (node (ref "U15") (pin "1") (pinfunction "1_1") (pintype "unspecified"))
    )
    (net (code "37") (name "/X_DIR_O") (class "Default")
      (node (ref "P7") (pin "2") (pinfunction "2_2") (pintype "unspecified"))
      (node (ref "U7") (pin "4") (pinfunction "Y_4") (pintype "unspecified"))
    )
    (net (code "38") (name "/X_LIMT") (class "Default")
      (node (ref "R2") (pin "2") (pinfunction "2_2") (pintype "unspecified"))
      (node (ref "U5") (pin "6") (pinfunction "IO34_6") (pintype "unspecified"))
    )
    (net (code "39") (name "/X_LIMT_I") (class "Default")
      (node (ref "C1") (pin "2") (pinfunction "2_2") (pintype "unspecified"))
      (node (ref "P2") (pin "1") (pinfunction "1_1") (pintype "unspecified"))
      (node (ref "R1") (pin "1") (pinfunction "1_1") (pintype "unspecified"))
      (node (ref "R2") (pin "1") (pinfunction "1_1") (pintype "unspecified"))
    )
    (net (code "40") (name "/X_STEP_O") (class "Default")
      (node (ref "P7") (pin "3") (pinfunction "3_3") (pintype "unspecified"))
      (node (ref "U6") (pin "10") (pinfunction "VO6_10") (pintype "unspecified"))
    )
    (net (code "41") (name "/Y_DIR_O") (class "Default")
      (node (ref "P10") (pin "2") (pinfunction "2_2") (pintype "unspecified"))
      (node (ref "P8") (pin "2") (pinfunction "2_2") (pintype "unspecified"))
      (node (ref "U6") (pin "11") (pinfunction "VO5_11") (pintype "unspecified"))
    )
    (net (code "42") (name "/Y_LIMT") (class "Default")
      (node (ref "R7") (pin "2") (pinfunction "2_2") (pintype "unspecified"))
      (node (ref "U5") (pin "5") (pinfunction "SENSOR_VN_5") (pintype "unspecified"))
    )
    (net (code "43") (name "/Y_LIMT_I") (class "Default")
      (node (ref "C5") (pin "2") (pinfunction "2_2") (pintype "unspecified"))
      (node (ref "P4") (pin "1") (pinfunction "1_1") (pintype "unspecified"))
      (node (ref "R5") (pin "1") (pinfunction "1_1") (pintype "unspecified"))
      (node (ref "R7") (pin "1") (pinfunction "1_1") (pintype "unspecified"))
    )
    (net (code "44") (name "/Y_STEP_O") (class "Default")
      (node (ref "P10") (pin "3") (pinfunction "3_3") (pintype "unspecified"))
      (node (ref "P8") (pin "3") (pinfunction "3_3") (pintype "unspecified"))
      (node (ref "U6") (pin "12") (pinfunction "VO4_12") (pintype "unspecified"))
    )
    (net (code "45") (name "/Z_DIR_O") (class "Default")
      (node (ref "P13") (pin "2") (pinfunction "2_2") (pintype "unspecified"))
      (node (ref "U6") (pin "13") (pinfunction "VO3_13") (pintype "unspecified"))
    )
    (net (code "46") (name "/Z_LIMT") (class "Default")
      (node (ref "R11") (pin "2") (pinfunction "2_2") (pintype "unspecified"))
      (node (ref "U5") (pin "4") (pinfunction "SENSOR_VP_4") (pintype "unspecified"))
    )
    (net (code "47") (name "/Z_LIMT_I") (class "Default")
      (node (ref "C12") (pin "2") (pinfunction "2_2") (pintype "unspecified"))
      (node (ref "P5") (pin "1") (pinfunction "1_1") (pintype "unspecified"))
      (node (ref "R10") (pin "1") (pinfunction "1_1") (pintype "unspecified"))
      (node (ref "R11") (pin "1") (pinfunction "1_1") (pintype "unspecified"))
    )
    (net (code "48") (name "/Z_STEP_O") (class "Default")
      (node (ref "P13") (pin "3") (pinfunction "3_3") (pintype "unspecified"))
      (node (ref "U6") (pin "14") (pinfunction "VO2_14") (pintype "unspecified"))
    )
    (net (code "49") (name "3V3") (class "Default")
      (node (ref "C10") (pin "2") (pinfunction "2_2") (pintype "input"))
      (node (ref "C11") (pin "2") (pinfunction "2_2") (pintype "unspecified"))
      (node (ref "C17") (pin "1") (pinfunction "1_1") (pintype "unspecified"))
      (node (ref "C27") (pin "2") (pinfunction "2_2") (pintype "unspecified"))
      (node (ref "C9") (pin "2") (pinfunction "2_2") (pintype "input"))
      (node (ref "D6") (pin "2") (pinfunction "2_2") (pintype "input"))
      (node (ref "R12") (pin "2") (pinfunction "2_2") (pintype "unspecified"))
      (node (ref "R18") (pin "1") (pinfunction "1_1") (pintype "unspecified"))
      (node (ref "R23") (pin "1") (pinfunction "1_1") (pintype "unspecified"))
      (node (ref "R36") (pin "2") (pinfunction "2_2") (pintype "unspecified"))
      (node (ref "R37") (pin "2") (pinfunction "2_2") (pintype "unspecified"))
      (node (ref "R38") (pin "2") (pinfunction "2_2") (pintype "unspecified"))
      (node (ref "R39") (pin "2") (pinfunction "2_2") (pintype "unspecified"))
      (node (ref "R43") (pin "1") (pinfunction "1_1") (pintype "input"))
      (node (ref "U14") (pin "4") (pinfunction "VDD_4") (pintype "unspecified"))
      (node (ref "U2") (pin "2") (pinfunction "OUT_2") (pintype "unspecified"))
      (node (ref "U2") (pin "4") (pinfunction "=_4") (pintype "unspecified"))
      (node (ref "U5") (pin "2") (pinfunction "3V3_2") (pintype "unspecified"))
      (node (ref "U6") (pin "1") (pinfunction "VDDA_1") (pintype "unspecified"))
    )
    (net (code "50") (name "5V_VCC") (class "Default")
      (node (ref "C16") (pin "2") (pinfunction "2_2") (pintype "unspecified"))
      (node (ref "C18") (pin "2") (pinfunction "2_2") (pintype "unspecified"))
      (node (ref "C19") (pin "2") (pinfunction "2_2") (pintype "unspecified"))
      (node (ref "C20") (pin "2") (pinfunction "2_2") (pintype "unspecified"))
      (node (ref "C21") (pin "2") (pinfunction "2_2") (pintype "unspecified"))
      (node (ref "C22") (pin "2") (pinfunction "2_2") (pintype "unspecified"))
      (node (ref "C23") (pin "2") (pinfunction "2_2") (pintype "unspecified"))
      (node (ref "C24") (pin "1") (pinfunction "1_1") (pintype "unspecified"))
      (node (ref "C6") (pin "1") (pinfunction "1_1") (pintype "input"))
      (node (ref "C7") (pin "2") (pinfunction "2_2") (pintype "unspecified"))
      (node (ref "C8") (pin "1") (pinfunction "1_1") (pintype "input"))
      (node (ref "D10") (pin "1") (pinfunction "c_1") (pintype "input"))
      (node (ref "D4") (pin "2") (pinfunction "2_2") (pintype "input"))
      (node (ref "L1") (pin "1") (pinfunction "1_1") (pintype "unspecified"))
      (node (ref "P10") (pin "1") (pinfunction "1_1") (pintype "unspecified"))
      (node (ref "P11") (pin "1") (pinfunction "1_1") (pintype "unspecified"))
      (node (ref "P13") (pin "1") (pinfunction "1_1") (pintype "unspecified"))
      (node (ref "P14") (pin "1") (pinfunction "1_1") (pintype "unspecified"))
      (node (ref "P16") (pin "1") (pinfunction "1_1") (pintype "unspecified"))
      (node (ref "P2") (pin "3") (pinfunction "3_3") (pintype "unspecified"))
      (node (ref "P3") (pin "3") (pinfunction "3_3") (pintype "unspecified"))
      (node (ref "P4") (pin "3") (pinfunction "3_3") (pintype "unspecified"))
      (node (ref "P5") (pin "3") (pinfunction "3_3") (pintype "unspecified"))
      (node (ref "P7") (pin "1") (pinfunction "1_1") (pintype "unspecified"))
      (node (ref "P8") (pin "1") (pinfunction "1_1") (pintype "unspecified"))
      (node (ref "P9") (pin "3") (pinfunction "3_3") (pintype "unspecified"))
      (node (ref "R1") (pin "2") (pinfunction "2_2") (pintype "unspecified"))
      (node (ref "R10") (pin "2") (pinfunction "2_2") (pintype "unspecified"))
      (node (ref "R19") (pin "1") (pinfunction "1_1") (pintype "unspecified"))
      (node (ref "R26") (pin "2") (pinfunction "2_2") (pintype "input"))
      (node (ref "R28") (pin "2") (pinfunction "2_2") (pintype "input"))
      (node (ref "R34") (pin "2") (pinfunction "2_2") (pintype "unspecified"))
      (node (ref "R4") (pin "2") (pinfunction "2_2") (pintype "unspecified"))
      (node (ref "R5") (pin "2") (pinfunction "2_2") (pintype "unspecified"))
      (node (ref "R8") (pin "2") (pinfunction "2_2") (pintype "unspecified"))
      (node (ref "U1") (pin "3") (pinfunction "FB_3") (pintype "input"))
      (node (ref "U10") (pin "5") (pinfunction "VCC_5") (pintype "unspecified"))
      (node (ref "U11") (pin "5") (pinfunction "VCC_5") (pintype "unspecified"))
      (node (ref "U12") (pin "5") (pinfunction "VCC_5") (pintype "unspecified"))
      (node (ref "U13") (pin "16") (pinfunction "VCC_16") (pintype "unspecified"))
      (node (ref "U2") (pin "3") (pinfunction "IN_3") (pintype "unspecified"))
      (node (ref "U3") (pin "5") (pinfunction "VCC_5") (pintype "unspecified"))
      (node (ref "U4") (pin "5") (pinfunction "VCC_5") (pintype "unspecified"))
      (node (ref "U6") (pin "16") (pinfunction "VDDB_16") (pintype "unspecified"))
      (node (ref "U7") (pin "5") (pinfunction "VCC_5") (pintype "unspecified"))
      (node (ref "U8") (pin "5") (pinfunction "VCC_5") (pintype "unspecified"))
      (node (ref "U9") (pin "5") (pinfunction "VCC_5") (pintype "unspecified"))
    )
    (net (code "51") (name "24V") (class "Default")
      (node (ref "C13") (pin "1") (pintype "unspecified"))
      (node (ref "D1") (pin "1") (pinfunction "1_1") (pintype "unspecified"))
      (node (ref "P1") (pin "2") (pinfunction "2_2") (pintype "input"))
      (node (ref "P15") (pin "1") (pinfunction "1_1") (pintype "unspecified"))
      (node (ref "P18") (pin "2") (pintype "input"))
      (node (ref "P19") (pin "2") (pintype "input"))
      (node (ref "P6") (pin "2") (pintype "input"))
      (node (ref "R13") (pin "1") (pintype "unspecified"))
      (node (ref "R14") (pin "2") (pintype "unspecified"))
      (node (ref "R3") (pin "2") (pinfunction "2_2") (pintype "unspecified"))
    )
    (net (code "52") (name "GND") (class "Default")
      (node (ref "C1") (pin "1") (pinfunction "1_1") (pintype "unspecified"))
      (node (ref "C10") (pin "1") (pinfunction "1_1") (pintype "input"))
      (node (ref "C11") (pin "1") (pinfunction "1_1") (pintype "unspecified"))
      (node (ref "C12") (pin "1") (pinfunction "1_1") (pintype "unspecified"))
      (node (ref "C14") (pin "1") (pinfunction "1_1") (pintype "unspecified"))
      (node (ref "C15") (pin "1") (pinfunction "1_1") (pintype "unspecified"))
      (node (ref "C16") (pin "1") (pinfunction "1_1") (pintype "unspecified"))
      (node (ref "C17") (pin "2") (pinfunction "2_2") (pintype "unspecified"))
      (node (ref "C18") (pin "1") (pinfunction "1_1") (pintype "unspecified"))
      (node (ref "C19") (pin "1") (pinfunction "1_1") (pintype "unspecified"))
      (node (ref "C2") (pin "2") (pintype "unspecified"))
      (node (ref "C20") (pin "1") (pinfunction "1_1") (pintype "unspecified"))
      (node (ref "C21") (pin "1") (pinfunction "1_1") (pintype "unspecified"))
      (node (ref "C22") (pin "1") (pinfunction "1_1") (pintype "unspecified"))
      (node (ref "C23") (pin "1") (pinfunction "1_1") (pintype "unspecified"))
      (node (ref "C24") (pin "2") (pinfunction "2_2") (pintype "unspecified"))
      (node (ref "C25") (pin "2") (pinfunction "2_2") (pintype "unspecified"))
      (node (ref "C26") (pin "2") (pinfunction "2_2") (pintype "unspecified"))
      (node (ref "C27") (pin "1") (pinfunction "1_1") (pintype "unspecified"))
      (node (ref "C28") (pin "2") (pinfunction "2_2") (pintype "unspecified"))
      (node (ref "C3") (pin "1") (pinfunction "1_1") (pintype "unspecified"))
      (node (ref "C4") (pin "1") (pinfunction "1_1") (pintype "unspecified"))
      (node (ref "C5") (pin "1") (pinfunction "1_1") (pintype "unspecified"))
      (node (ref "C6") (pin "2") (pinfunction "2_2") (pintype "input"))
      (node (ref "C7") (pin "1") (pinfunction "1_1") (pintype "unspecified"))
      (node (ref "C8") (pin "2") (pinfunction "2_2") (pintype "input"))
      (node (ref "C9") (pin "1") (pinfunction "1_1") (pintype "input"))
      (node (ref "D2") (pin "1") (pinfunction "1_1") (pintype "input"))
      (node (ref "D3") (pin "2") (pinfunction "2_2") (pintype "unspecified"))
      (node (ref "D4") (pin "1") (pinfunction "1_1") (pintype "input"))
      (node (ref "D5") (pin "2") (pinfunction "2_2") (pintype "unspecified"))
      (node (ref "D6") (pin "1") (pinfunction "1_1") (pintype "input"))
      (node (ref "D7") (pin "2") (pinfunction "2_2") (pintype "unspecified"))
      (node (ref "DZ1") (pin "1") (pinfunction "1_1") (pintype "input"))
      (node (ref "K1") (pin "1") (pinfunction "1_1") (pintype "unspecified"))
      (node (ref "K1") (pin "2") (pinfunction "2_2") (pintype "unspecified"))
      (node (ref "K2") (pin "1") (pinfunction "1_1") (pintype "unspecified"))
      (node (ref "P1") (pin "1") (pinfunction "1_1") (pintype "input"))
      (node (ref "P11") (pin "3") (pinfunction "3_3") (pintype "unspecified"))
      (node (ref "P12") (pin "2") (pintype "input"))
      (node (ref "P15") (pin "3") (pinfunction "3_3") (pintype "unspecified"))
      (node (ref "P16") (pin "3") (pinfunction "3_3") (pintype "unspecified"))
      (node (ref "P17") (pin "4") (pinfunction "GND_4") (pintype "unspecified"))
      (node (ref "P17") (pin "5") (pinfunction "GND_5") (pintype "unspecified"))
      (node (ref "P17") (pin "6") (pinfunction "GND_6") (pintype "unspecified"))
      (node (ref "P18") (pin "1") (pintype "input"))
      (node (ref "P19") (pin "1") (pintype "input"))
      (node (ref "P2") (pin "2") (pinfunction "2_2") (pintype "unspecified"))
      (node (ref "P3") (pin "2") (pinfunction "2_2") (pintype "unspecified"))
      (node (ref "P4") (pin "2") (pinfunction "2_2") (pintype "unspecified"))
      (node (ref "P5") (pin "2") (pinfunction "2_2") (pintype "unspecified"))
      (node (ref "P9") (pin "2") (pinfunction "2_2") (pintype "unspecified"))
      (node (ref "Q1") (pin "3") (pinfunction "S_3") (pintype "unspecified"))
      (node (ref "Q3") (pin "2") (pinfunction "E_2") (pintype "input"))
      (node (ref "R15") (pin "1") (pintype "unspecified"))
      (node (ref "R17") (pin "1") (pinfunction "1_1") (pintype "unspecified"))
      (node (ref "R22") (pin "2") (pinfunction "2_2") (pintype "input"))
      (node (ref "R24") (pin "2") (pinfunction "2_2") (pintype "input"))
      (node (ref "R25") (pin "2") (pinfunction "2_2") (pintype "input"))
      (node (ref "R27") (pin "2") (pinfunction "2_2") (pintype "input"))
      (node (ref "R29") (pin "2") (pinfunction "2_2") (pintype "input"))
      (node (ref "R30") (pin "2") (pinfunction "2_2") (pintype "input"))
      (node (ref "R31") (pin "2") (pinfunction "2_2") (pintype "input"))
      (node (ref "R9") (pin "2") (pinfunction "2_2") (pintype "unspecified"))
      (node (ref "U1") (pin "5") (pinfunction "GND_5") (pintype "input"))
      (node (ref "U1") (pin "6") (pinfunction "GND_6") (pintype "input"))
      (node (ref "U1") (pin "7") (pinfunction "GND_7") (pintype "input"))
      (node (ref "U1") (pin "8") (pinfunction "GND_8") (pintype "input"))
      (node (ref "U10") (pin "3") (pinfunction "GND_3") (pintype "unspecified"))
      (node (ref "U11") (pin "3") (pinfunction "GND_3") (pintype "unspecified"))
      (node (ref "U12") (pin "3") (pinfunction "GND_3") (pintype "unspecified"))
      (node (ref "U13") (pin "1") (pinfunction "GND_1") (pintype "unspecified"))
      (node (ref "U14") (pin "10") (pinfunction "GND_10") (pintype "unspecified"))
      (node (ref "U14") (pin "11") (pinfunction "GND_11") (pintype "unspecified"))
      (node (ref "U14") (pin "12") (pinfunction "GND_12") (pintype "unspecified"))
      (node (ref "U14") (pin "13") (pinfunction "GND_13") (pintype "unspecified"))
      (node (ref "U14") (pin "6") (pinfunction "VSS_6") (pintype "unspecified"))
      (node (ref "U15") (pin "2") (pinfunction "2_2") (pintype "unspecified"))
      (node (ref "U2") (pin "1") (pinfunction "GND_1") (pintype "unspecified"))
      (node (ref "U3") (pin "3") (pinfunction "GND_3") (pintype "unspecified"))
      (node (ref "U4") (pin "3") (pinfunction "GND_3") (pintype "unspecified"))
      (node (ref "U5") (pin "1") (pinfunction "GND_1") (pintype "unspecified"))
      (node (ref "U5") (pin "15") (pinfunction "GND_15") (pintype "unspecified"))
      (node (ref "U5") (pin "38") (pinfunction "GND_38") (pintype "unspecified"))
      (node (ref "U5") (pin "39") (pinfunction "EP_39") (pintype "unspecified"))
      (node (ref "U6") (pin "8") (pinfunction "GNDA_8") (pintype "unspecified"))
      (node (ref "U6") (pin "9") (pinfunction "GNDB_9") (pintype "unspecified"))
      (node (ref "U7") (pin "3") (pinfunction "GND_3") (pintype "unspecified"))
      (node (ref "U8") (pin "3") (pinfunction "GND_3") (pintype "unspecified"))
      (node (ref "U9") (pin "3") (pinfunction "GND_3") (pintype "unspecified"))
    )
    (net (code "53") (name "Net-(C14-Pad2)") (class "Default")
      (node (ref "C14") (pin "2") (pinfunction "2_2") (pintype "unspecified"))
      (node (ref "K1") (pin "3") (pinfunction "3_3") (pintype "unspecified"))
      (node (ref "K1") (pin "4") (pinfunction "4_4") (pintype "unspecified"))
      (node (ref "P12") (pin "1") (pintype "input"))
      (node (ref "R18") (pin "2") (pinfunction "2_2") (pintype "unspecified"))
      (node (ref "R20") (pin "2") (pinfunction "2_2") (pintype "input"))
    )
    (net (code "54") (name "Net-(C15-Pad2)") (class "Default")
      (node (ref "C15") (pin "2") (pinfunction "2_2") (pintype "unspecified"))
      (node (ref "P11") (pin "2") (pinfunction "2_2") (pintype "unspecified"))
      (node (ref "R19") (pin "2") (pinfunction "2_2") (pintype "unspecified"))
      (node (ref "R21") (pin "2") (pinfunction "2_2") (pintype "input"))
    )
    (net (code "55") (name "Net-(D3-Pad1)") (class "Default")
      (node (ref "D3") (pin "1") (pinfunction "1_1") (pintype "unspecified"))
      (node (ref "R3") (pin "1") (pinfunction "1_1") (pintype "unspecified"))
    )
    (net (code "56") (name "Net-(D5-Pad1)") (class "Default")
      (node (ref "D5") (pin "1") (pinfunction "1_1") (pintype "unspecified"))
      (node (ref "R8") (pin "1") (pinfunction "1_1") (pintype "unspecified"))
    )
    (net (code "57") (name "Net-(D7-Pad1)") (class "Default")
      (node (ref "D7") (pin "1") (pinfunction "1_1") (pintype "unspecified"))
      (node (ref "R12") (pin "1") (pinfunction "1_1") (pintype "unspecified"))
    )
    (net (code "58") (name "Net-(D8-Pad1)") (class "Default")
      (node (ref "D8") (pin "1") (pinfunction "1_1") (pintype "unspecified"))
      (node (ref "R13") (pin "2") (pintype "unspecified"))
    )
    (net (code "59") (name "Net-(Q1-D)") (class "Default")
      (node (ref "C13") (pin "2") (pintype "unspecified"))
      (node (ref "D8") (pin "2") (pinfunction "2_2") (pintype "unspecified"))
      (node (ref "P6") (pin "1") (pintype "input"))
      (node (ref "Q1") (pin "2") (pinfunction "D_2") (pintype "unspecified"))
    )
    (net (code "60") (name "Net-(Q1-G)") (class "Default")
      (node (ref "DZ1") (pin "2") (pinfunction "2_2") (pintype "input"))
      (node (ref "Q1") (pin "1") (pinfunction "G_1") (pintype "unspecified"))
      (node (ref "Q2") (pin "2") (pinfunction "E_2") (pintype "unspecified"))
      (node (ref "R15") (pin "2") (pintype "unspecified"))
    )
    (net (code "61") (name "Net-(Q2-B)") (class "Default")
      (node (ref "Q2") (pin "1") (pinfunction "B_1") (pintype "unspecified"))
      (node (ref "R16") (pin "1") (pintype "unspecified"))
    )
    (net (code "62") (name "Net-(Q2-C)") (class "Default")
      (node (ref "Q2") (pin "3") (pinfunction "C_3") (pintype "unspecified"))
      (node (ref "R14") (pin "1") (pintype "unspecified"))
    )
    (net (code "63") (name "Net-(Q3-B)") (class "Default")
      (node (ref "Q3") (pin "1") (pinfunction "B_1") (pintype "input"))
      (node (ref "R28") (pin "1") (pinfunction "1_1") (pintype "input"))
      (node (ref "R32") (pin "2") (pinfunction "2_2") (pintype "input"))
    )
    (net (code "64") (name "Net-(Q4-B)") (class "Default")
      (node (ref "Q4") (pin "1") (pinfunction "B_1") (pintype "unspecified"))
      (node (ref "R35") (pin "2") (pinfunction "2_2") (pintype "unspecified"))
    )
    (net (code "65") (name "Net-(Q4-E)") (class "Default")
      (node (ref "Q4") (pin "2") (pinfunction "E_2") (pintype "unspecified"))
      (node (ref "R40") (pin "1") (pinfunction "1_1") (pintype "unspecified"))
      (node (ref "U13") (pin "13") (pinfunction "DTR#_13") (pintype "unspecified"))
    )
    (net (code "66") (name "Net-(Q5-B)") (class "Default")
      (node (ref "Q5") (pin "1") (pinfunction "B_1") (pintype "unspecified"))
      (node (ref "R40") (pin "2") (pinfunction "2_2") (pintype "unspecified"))
    )
    (net (code "67") (name "Net-(Q5-E)") (class "Default")
      (node (ref "Q5") (pin "2") (pinfunction "E_2") (pintype "unspecified"))
      (node (ref "R35") (pin "1") (pinfunction "1_1") (pintype "unspecified"))
      (node (ref "U13") (pin "14") (pinfunction "RTS#_14") (pintype "unspecified"))
    )
    (net (code "68") (name "Net-(U1-ON{slash}OFF)") (class "Default")
      (node (ref "R9") (pin "1") (pinfunction "1_1") (pintype "unspecified"))
      (node (ref "U1") (pin "4") (pinfunction "ON/OFF_4") (pintype "input"))
    )
    (net (code "69") (name "Net-(U1-OUTPUT)") (class "Default")
      (node (ref "D2") (pin "2") (pinfunction "2_2") (pintype "input"))
      (node (ref "L1") (pin "2") (pinfunction "2_2") (pintype "unspecified"))
      (node (ref "U1") (pin "2") (pinfunction "OUTPUT_2") (pintype "input"))
    )
    (net (code "70") (name "Net-(U8-A)") (class "Default")
      (node (ref "R25") (pin "1") (pinfunction "1_1") (pintype "input"))
      (node (ref "U8") (pin "2") (pinfunction "A_2") (pintype "unspecified"))
    )
    (net (code "71") (name "Net-(U13-RXD)") (class "Default")
      (node (ref "R34") (pin "1") (pinfunction "1_1") (pintype "unspecified"))
      (node (ref "R41") (pin "2") (pinfunction "2_2") (pintype "input"))
      (node (ref "U13") (pin "3") (pinfunction "RXD_3") (pintype "unspecified"))
    )
    (net (code "72") (name "Net-(U13-TXD)") (class "Default")
      (node (ref "R42") (pin "2") (pinfunction "2_2") (pintype "input"))
      (node (ref "U13") (pin "2") (pinfunction "TXD_2") (pintype "unspecified"))
    )
    (net (code "73") (name "Net-(U13-UD+)") (class "Default")
      (node (ref "U13") (pin "5") (pinfunction "UD+_5") (pintype "unspecified"))
      (node (ref "U15") (pin "6") (pinfunction "6_6") (pintype "unspecified"))
    )
    (net (code "74") (name "Net-(U13-UD-)") (class "Default")
      (node (ref "U13") (pin "6") (pinfunction "UD-_6") (pintype "unspecified"))
      (node (ref "U15") (pin "4") (pinfunction "4_4") (pintype "unspecified"))
    )
    (net (code "75") (name "Net-(U13-V3)") (class "Default")
      (node (ref "C25") (pin "1") (pinfunction "1_1") (pintype "unspecified"))
      (node (ref "U13") (pin "4") (pinfunction "V3_4") (pintype "unspecified"))
    )
    (net (code "76") (name "Net-(U13-XI)") (class "Default")
      (node (ref "C26") (pin "1") (pinfunction "1_1") (pintype "unspecified"))
      (node (ref "U13") (pin "7") (pinfunction "XI_7") (pintype "unspecified"))
      (node (ref "Y1") (pin "2") (pinfunction "OSC2_2") (pintype "unspecified"))
    )
    (net (code "77") (name "Net-(U13-XO)") (class "Default")
      (node (ref "C28") (pin "1") (pinfunction "1_1") (pintype "unspecified"))
      (node (ref "U13") (pin "8") (pinfunction "XO_8") (pintype "unspecified"))
      (node (ref "Y1") (pin "1") (pinfunction "OSC1_1") (pintype "unspecified"))
    )
    (net (code "78") (name "VIN_24V") (class "Default")
      (node (ref "C2") (pin "1") (pintype "unspecified"))
      (node (ref "C3") (pin "2") (pinfunction "2_2") (pintype "unspecified"))
      (node (ref "D1") (pin "2") (pinfunction "2_2") (pintype "unspecified"))
      (node (ref "U1") (pin "1") (pinfunction "VIN_1") (pintype "input"))
    )
    (net (code "79") (name "VUSB") (class "Default")
      (node (ref "D10") (pin "2") (pinfunction "A_2") (pintype "input"))
      (node (ref "P17") (pin "1") (pinfunction "VBUS_1") (pintype "unspecified"))
      (node (ref "U15") (pin "5") (pinfunction "5_5") (pintype "unspecified"))
    )
    (net (code "80") (name "unconnected-(U3-NC-Pad1)") (class "Default")
      (node (ref "U3") (pin "1") (pinfunction "NC_1") (pintype "unspecified"))
    )
    (net (code "81") (name "unconnected-(U4-NC-Pad1)") (class "Default")
      (node (ref "U4") (pin "1") (pinfunction "NC_1") (pintype "unspecified"))
    )
    (net (code "82") (name "unconnected-(U5-CLK-Pad20)") (class "Default")
      (node (ref "U5") (pin "20") (pinfunction "CLK_20") (pintype "unspecified"))
    )
    (net (code "83") (name "unconnected-(U5-CMD-Pad19)") (class "Default")
      (node (ref "U5") (pin "19") (pinfunction "CMD_19") (pintype "unspecified"))
    )
    (net (code "84") (name "unconnected-(U5-NC-Pad32)") (class "Default")
      (node (ref "U5") (pin "32") (pinfunction "NC_32") (pintype "unspecified"))
    )
    (net (code "85") (name "unconnected-(U5-SD0-Pad21)") (class "Default")
      (node (ref "U5") (pin "21") (pinfunction "SD0_21") (pintype "unspecified"))
    )
    (net (code "86") (name "unconnected-(U5-SD1-Pad22)") (class "Default")
      (node (ref "U5") (pin "22") (pinfunction "SD1_22") (pintype "unspecified"))
    )
    (net (code "87") (name "unconnected-(U5-SD2-Pad17)") (class "Default")
      (node (ref "U5") (pin "17") (pinfunction "SD2_17") (pintype "unspecified"))
    )
    (net (code "88") (name "unconnected-(U5-SD3-Pad18)") (class "Default")
      (node (ref "U5") (pin "18") (pinfunction "SD3_18") (pintype "unspecified"))
    )
    (net (code "89") (name "unconnected-(U7-NC-Pad1)") (class "Default")
      (node (ref "U7") (pin "1") (pinfunction "NC_1") (pintype "unspecified"))
    )
    (net (code "90") (name "unconnected-(U8-NC-Pad1)") (class "Default")
      (node (ref "U8") (pin "1") (pinfunction "NC_1") (pintype "unspecified"))
    )
    (net (code "91") (name "unconnected-(U8-Y-Pad4)") (class "Default")
      (node (ref "U8") (pin "4") (pinfunction "Y_4") (pintype "unspecified"))
    )
    (net (code "92") (name "unconnected-(U9-NC-Pad1)") (class "Default")
      (node (ref "U9") (pin "1") (pinfunction "NC_1") (pintype "unspecified"))
    )
    (net (code "93") (name "unconnected-(U10-NC-Pad1)") (class "Default")
      (node (ref "U10") (pin "1") (pinfunction "NC_1") (pintype "unspecified"))
    )
    (net (code "94") (name "unconnected-(U11-NC-Pad1)") (class "Default")
      (node (ref "U11") (pin "1") (pinfunction "NC_1") (pintype "unspecified"))
    )
    (net (code "95") (name "unconnected-(U12-NC-Pad1)") (class "Default")
      (node (ref "U12") (pin "1") (pinfunction "NC_1") (pintype "unspecified"))
    )
    (net (code "96") (name "unconnected-(U13-CTS#-Pad9)") (class "Default")
      (node (ref "U13") (pin "9") (pinfunction "CTS#_9") (pintype "unspecified"))
    )
    (net (code "97") (name "unconnected-(U13-DCD#-Pad12)") (class "Default")
      (node (ref "U13") (pin "12") (pinfunction "DCD#_12") (pintype "unspecified"))
    )
    (net (code "98") (name "unconnected-(U13-DSR#-Pad10)") (class "Default")
      (node (ref "U13") (pin "10") (pinfunction "DSR#_10") (pintype "unspecified"))
    )
    (net (code "99") (name "unconnected-(U13-R232-Pad15)") (class "Default")
      (node (ref "U13") (pin "15") (pinfunction "R232_15") (pintype "unspecified"))
    )
    (net (code "100") (name "unconnected-(U13-RI#-Pad11)") (class "Default")
      (node (ref "U13") (pin "11") (pinfunction "RI#_11") (pintype "unspecified"))
    )
    (net (code "101") (name "unconnected-(U14-DAT1-Pad8)") (class "Default")
      (node (ref "U14") (pin "8") (pinfunction "DAT1_8") (pintype "unspecified"))
    )
    (net (code "102") (name "unconnected-(U14-DAT2-Pad1)") (class "Default")
      (node (ref "U14") (pin "1") (pinfunction "DAT2_1") (pintype "unspecified"))
    )
  )
)
